# 6digit-ADC-display.net
KiCad netlist of a schematic drawn in EAGLE
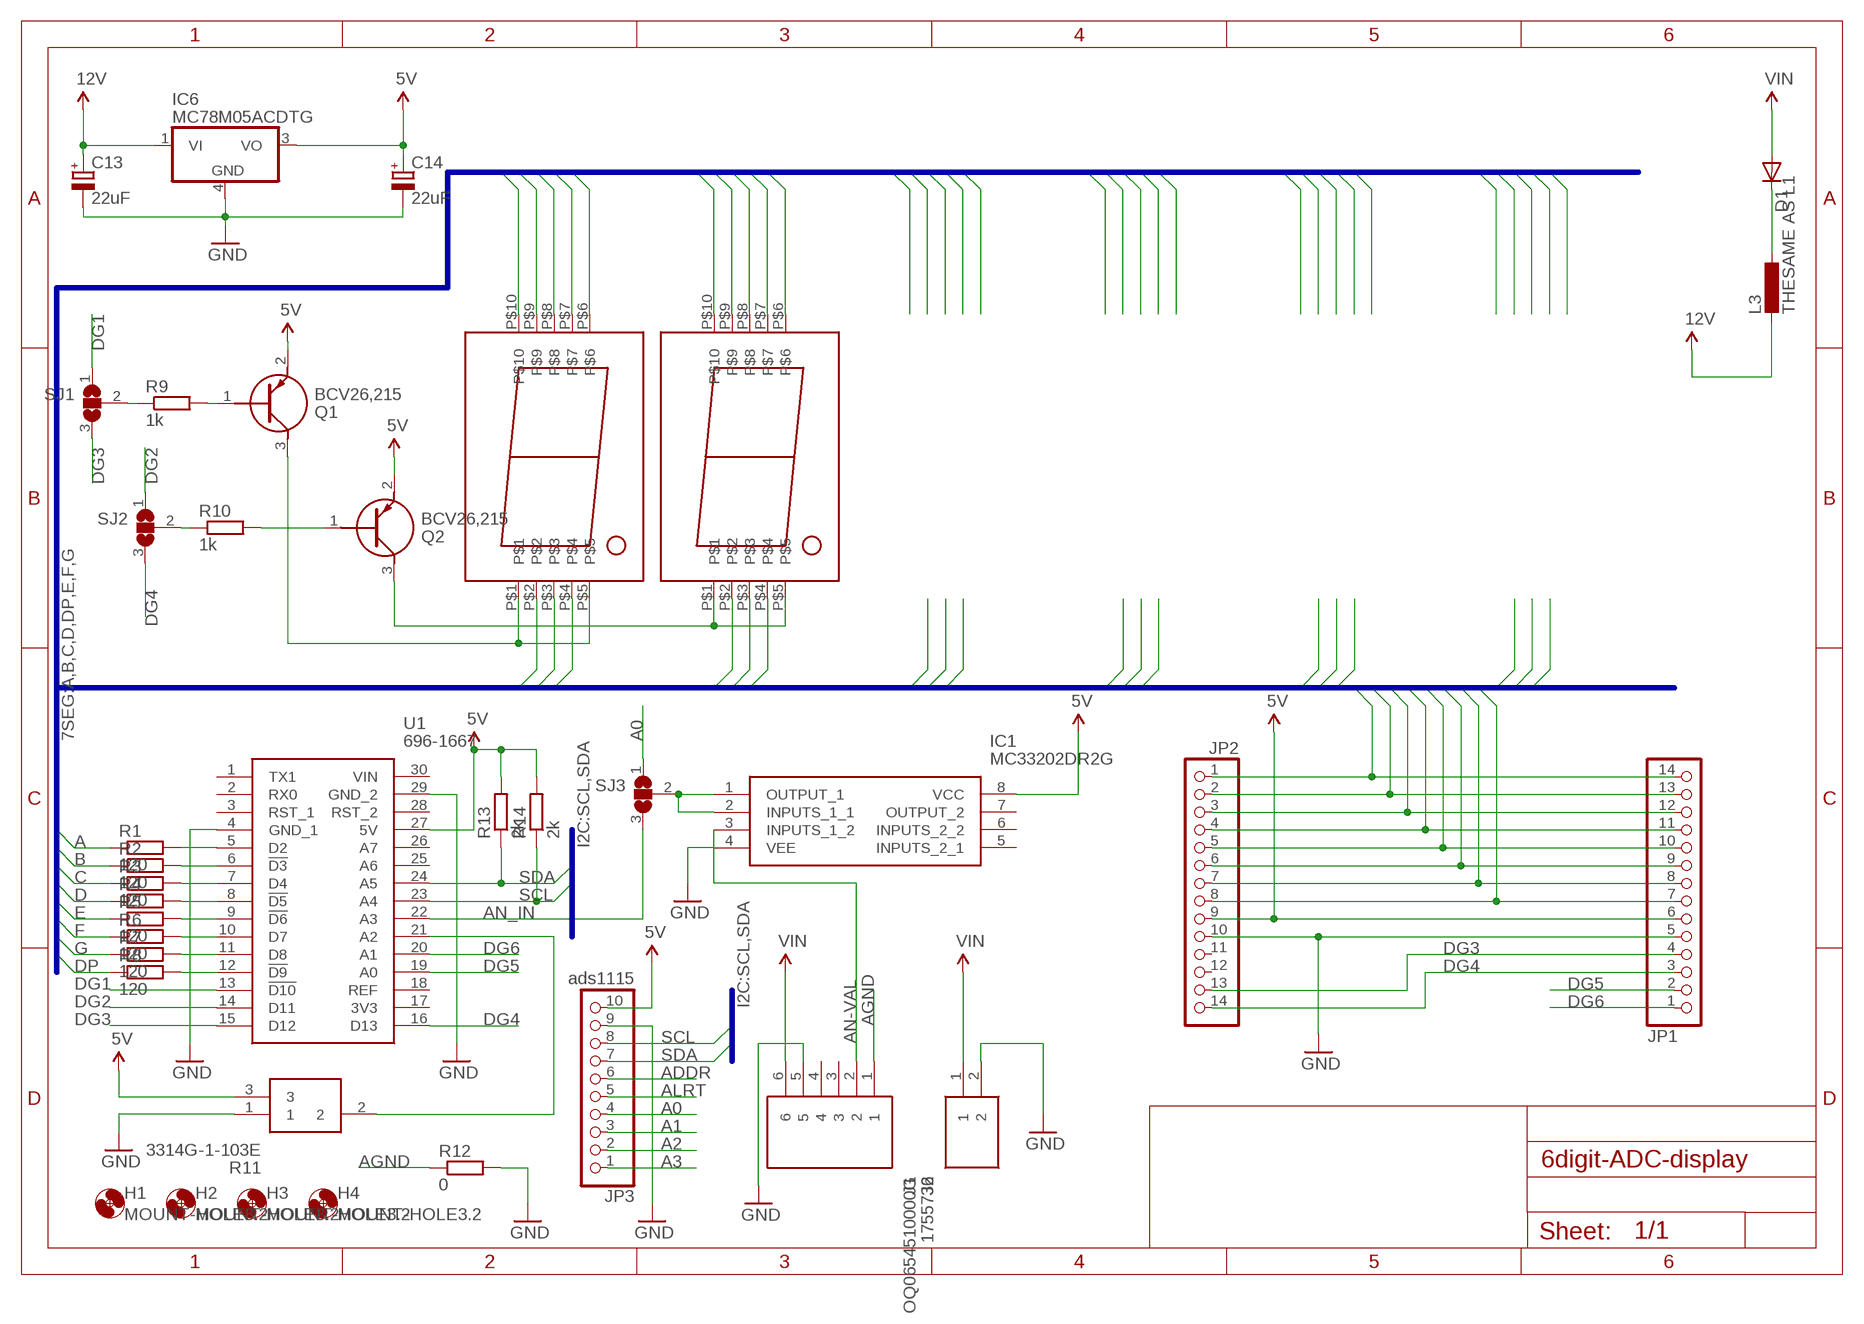
[diagram p0: schematic, sheet 1]

(export (version "E")
  (design (tool "Eeschema 10.0.6"))
  (components
    (comp (ref "C13")
      (value "22uF")
      (footprint "eagle-import:E2,5-7")
      (libsource (lib "eagle-import") (part "CPOL-EUE2.5-7"))
    )
    (comp (ref "C14")
      (value "22uF")
      (footprint "eagle-import:E2,5-7")
      (libsource (lib "eagle-import") (part "CPOL-EUE2.5-7"))
    )
    (comp (ref "D1")
      (value "DIODE-DO-214AC")
      (footprint "eagle-import:DO-214AC")
      (libsource (lib "eagle-import") (part "DIODE-DO-214AC"))
    )
    (comp (ref "H1")
      (value "MOUNT-HOLE3.2")
      (footprint "eagle-import:3,2")
      (libsource (lib "eagle-import") (part "MOUNT-HOLE3.2"))
    )
    (comp (ref "H2")
      (value "MOUNT-HOLE3.2")
      (footprint "eagle-import:3,2")
      (libsource (lib "eagle-import") (part "MOUNT-HOLE3.2"))
    )
    (comp (ref "H3")
      (value "MOUNT-HOLE3.2")
      (footprint "eagle-import:3,2")
      (libsource (lib "eagle-import") (part "MOUNT-HOLE3.2"))
    )
    (comp (ref "H4")
      (value "MOUNT-HOLE3.2")
      (footprint "eagle-import:3,2")
      (libsource (lib "eagle-import") (part "MOUNT-HOLE3.2"))
    )
    (comp (ref "IC1")
      (value "MC33202DR2G")
      (footprint "eagle-import:SOIC127P600X175-8N")
      (fields (field (name "MOUSER_PART_NUMBER") "863-MC33202DR2G"))
      (libsource (lib "eagle-import") (part "MC33202DR2G"))
    )
    (comp (ref "IC6")
      (value "MC78M05ACDTG")
      (footprint "eagle-import:DPACK_3")
      (libsource (lib "eagle-import") (part "MC78M05ACDTG"))
    )
    (comp (ref "J1")
      (value "1755736")
      (footprint "eagle-import:SHDR2W100P0X508_1X2_1216X860X1")
      (fields (field (name "MOUSER_PART_NUMBER") "651-1755736"))
      (libsource (lib "eagle-import") (part "1755736"))
    )
    (comp (ref "J2")
      (value "OQ0654510000G")
      (footprint "eagle-import:SHDRRA6W100P0X508_1X6_3248X120")
      (fields (field (name "MOUSER_PART_NUMBER") "649-OQ06545100J0G"))
      (libsource (lib "eagle-import") (part "OQ0654510000G"))
    )
    (comp (ref "JP1")
      (value "PINHD-1X14/90")
      (footprint "eagle-import:1X14_90")
      (libsource (lib "eagle-import") (part "PINHD-1X14/90"))
    )
    (comp (ref "JP2")
      (value "PINHD-1X14/90")
      (footprint "eagle-import:1X14_90")
      (libsource (lib "eagle-import") (part "PINHD-1X14/90"))
    )
    (comp (ref "JP3")
      (value "ads1115")
      (footprint "eagle-import:1X10")
      (libsource (lib "eagle-import") (part "PINHD-1X10"))
    )
    (comp (ref "L3")
      (value "THESAME AS L1")
      (footprint "eagle-import:L1812")
      (libsource (lib "eagle-import") (part "L-EUL1812"))
    )
    (comp (ref "Q1")
      (value "BCV26,215")
      (footprint "eagle-import:SOT95P230X110-3N")
      (fields (field (name "MOUSER_PART_NUMBER") "771-BCV26215"))
      (libsource (lib "eagle-import") (part "BCV26,215"))
    )
    (comp (ref "Q2")
      (value "BCV26,215")
      (footprint "eagle-import:SOT95P230X110-3N")
      (fields (field (name "MOUSER_PART_NUMBER") "771-BCV26215"))
      (libsource (lib "eagle-import") (part "BCV26,215"))
    )
    (comp (ref "R1")
      (value "120")
      (footprint "eagle-import:R0805")
      (libsource (lib "eagle-import") (part "R-EU_R0805"))
    )
    (comp (ref "R2")
      (value "120")
      (footprint "eagle-import:R0805")
      (libsource (lib "eagle-import") (part "R-EU_R0805"))
    )
    (comp (ref "R3")
      (value "120")
      (footprint "eagle-import:R0805")
      (libsource (lib "eagle-import") (part "R-EU_R0805"))
    )
    (comp (ref "R4")
      (value "R-EU_R0805")
      (footprint "eagle-import:R0805")
      (libsource (lib "eagle-import") (part "R-EU_R0805"))
    )
    (comp (ref "R5")
      (value "120")
      (footprint "eagle-import:R0805")
      (libsource (lib "eagle-import") (part "R-EU_R0805"))
    )
    (comp (ref "R6")
      (value "120")
      (footprint "eagle-import:R0805")
      (libsource (lib "eagle-import") (part "R-EU_R0805"))
    )
    (comp (ref "R7")
      (value "120")
      (footprint "eagle-import:R0805")
      (libsource (lib "eagle-import") (part "R-EU_R0805"))
    )
    (comp (ref "R8")
      (value "120")
      (footprint "eagle-import:R0805")
      (libsource (lib "eagle-import") (part "R-EU_R0805"))
    )
    (comp (ref "R9")
      (value "1k")
      (footprint "eagle-import:R0805")
      (libsource (lib "eagle-import") (part "R-EU_R0805"))
    )
    (comp (ref "R10")
      (value "1k")
      (footprint "eagle-import:R0805")
      (libsource (lib "eagle-import") (part "R-EU_R0805"))
    )
    (comp (ref "R11")
      (value "3314G-1-103E")
      (footprint "eagle-import:3314G-1-102E")
      (fields (field (name "MOUSER_PART_NUMBER") "652-3314G-1-103E"))
      (libsource (lib "eagle-import") (part "3314G-1-103E"))
    )
    (comp (ref "R12")
      (value "0")
      (footprint "eagle-import:R0805")
      (libsource (lib "eagle-import") (part "R-EU_R0805"))
    )
    (comp (ref "R13")
      (value "2k")
      (footprint "eagle-import:R0805")
      (libsource (lib "eagle-import") (part "R-EU_R0805"))
    )
    (comp (ref "R14")
      (value "2k")
      (footprint "eagle-import:R0805")
      (libsource (lib "eagle-import") (part "R-EU_R0805"))
    )
    (comp (ref "SJ1")
      (value "SJ2W")
      (footprint "eagle-import:SJ_2")
      (libsource (lib "eagle-import") (part "SJ2W"))
    )
    (comp (ref "SJ2")
      (value "SJ2W")
      (footprint "eagle-import:SJ_2")
      (libsource (lib "eagle-import") (part "SJ2W"))
    )
    (comp (ref "SJ3")
      (value "SJ2W")
      (footprint "eagle-import:SJ_2")
      (libsource (lib "eagle-import") (part "SJ2W"))
    )
    (comp (ref "U$1")
      (value "TOS-23101BMRL-B")
      (footprint "eagle-import:TOS-23101BMRL-B")
      (libsource (lib "eagle-import") (part "TOS-23101BMRL-B"))
    )
    (comp (ref "U$2")
      (value "TOS-23101BMRL-B")
      (footprint "eagle-import:TOS-23101BMRL-B")
      (libsource (lib "eagle-import") (part "TOS-23101BMRL-B"))
    )
    (comp (ref "U1")
      (value "696-1667")
      (footprint "eagle-import:6961667")
      (libsource (lib "eagle-import") (part "696-1667"))
    )
  )
  (nets
    (net (code "3") (name "/A") (class "Default")
      (node (ref "JP1") (pin "14") (pinfunction "14_14") (pintype "passive"))
      (node (ref "JP2") (pin "1") (pinfunction "1_1") (pintype "passive"))
      (node (ref "R1") (pin "1") (pinfunction "1_1") (pintype "passive"))
      (node (ref "U$1") (pin "P$7") (pinfunction "P$7_P$7") (pintype "bidirectional"))
      (node (ref "U$2") (pin "P$7") (pinfunction "P$7_P$7") (pintype "bidirectional"))
    )
    (net (code "4") (name "/A0") (class "Default")
      (node (ref "JP3") (pin "4") (pinfunction "4_4") (pintype "passive"))
      (node (ref "SJ3") (pin "1") (pinfunction "1_1") (pintype "passive"))
    )
    (net (code "5") (name "/A1") (class "Default")
      (node (ref "JP3") (pin "3") (pinfunction "3_3") (pintype "passive"))
    )
    (net (code "6") (name "/A2") (class "Default")
      (node (ref "JP3") (pin "2") (pinfunction "2_2") (pintype "passive"))
    )
    (net (code "7") (name "/A3") (class "Default")
      (node (ref "JP3") (pin "1") (pinfunction "1_1") (pintype "passive"))
    )
    (net (code "8") (name "/ADDR") (class "Default")
      (node (ref "JP3") (pin "6") (pinfunction "6_6") (pintype "passive"))
    )
    (net (code "9") (name "/AGND") (class "Default")
      (node (ref "J2") (pin "1") (pinfunction "1_1") (pintype "bidirectional"))
      (node (ref "R12") (pin "1") (pinfunction "1_1") (pintype "passive"))
    )
    (net (code "10") (name "/ALRT") (class "Default")
      (node (ref "JP3") (pin "5") (pinfunction "5_5") (pintype "passive"))
    )
    (net (code "11") (name "/AN-VAL") (class "Default")
      (node (ref "IC1") (pin "3") (pinfunction "INPUTS_1_2_3") (pintype "bidirectional"))
      (node (ref "J2") (pin "2") (pinfunction "2_2") (pintype "bidirectional"))
    )
    (net (code "12") (name "/AN_IN") (class "Default")
      (node (ref "SJ3") (pin "3") (pinfunction "3_3") (pintype "passive"))
      (node (ref "U1") (pin "22") (pinfunction "A3_22") (pintype "bidirectional"))
    )
    (net (code "13") (name "/B") (class "Default")
      (node (ref "JP1") (pin "13") (pinfunction "13_13") (pintype "passive"))
      (node (ref "JP2") (pin "2") (pinfunction "2_2") (pintype "passive"))
      (node (ref "R2") (pin "1") (pinfunction "1_1") (pintype "passive"))
      (node (ref "U$1") (pin "P$6") (pinfunction "P$6_P$6") (pintype "bidirectional"))
      (node (ref "U$2") (pin "P$6") (pinfunction "P$6_P$6") (pintype "bidirectional"))
    )
    (net (code "14") (name "/C") (class "Default")
      (node (ref "JP1") (pin "12") (pinfunction "12_12") (pintype "passive"))
      (node (ref "JP2") (pin "3") (pinfunction "3_3") (pintype "passive"))
      (node (ref "R3") (pin "1") (pinfunction "1_1") (pintype "passive"))
      (node (ref "U$1") (pin "P$4") (pinfunction "P$4_P$4") (pintype "bidirectional"))
      (node (ref "U$2") (pin "P$4") (pinfunction "P$4_P$4") (pintype "bidirectional"))
    )
    (net (code "15") (name "/D") (class "Default")
      (node (ref "JP1") (pin "11") (pinfunction "11_11") (pintype "passive"))
      (node (ref "JP2") (pin "4") (pinfunction "4_4") (pintype "passive"))
      (node (ref "R4") (pin "1") (pinfunction "1_1") (pintype "passive"))
      (node (ref "U$1") (pin "P$3") (pinfunction "P$3_P$3") (pintype "bidirectional"))
      (node (ref "U$2") (pin "P$3") (pinfunction "P$3_P$3") (pintype "bidirectional"))
    )
    (net (code "16") (name "/DG1") (class "Default")
      (node (ref "SJ1") (pin "1") (pinfunction "1_1") (pintype "passive"))
      (node (ref "U1") (pin "13") (pinfunction "~{D10}_13") (pintype "bidirectional"))
    )
    (net (code "17") (name "/DG2") (class "Default")
      (node (ref "SJ2") (pin "1") (pinfunction "1_1") (pintype "passive"))
      (node (ref "U1") (pin "14") (pinfunction "D11_14") (pintype "bidirectional"))
    )
    (net (code "18") (name "/DG3") (class "Default")
      (node (ref "JP1") (pin "4") (pinfunction "4_4") (pintype "passive"))
      (node (ref "JP2") (pin "13") (pinfunction "13_13") (pintype "passive"))
      (node (ref "SJ1") (pin "3") (pinfunction "3_3") (pintype "passive"))
      (node (ref "U1") (pin "15") (pinfunction "D12_15") (pintype "bidirectional"))
    )
    (net (code "19") (name "/DG4") (class "Default")
      (node (ref "JP1") (pin "3") (pinfunction "3_3") (pintype "passive"))
      (node (ref "JP2") (pin "14") (pinfunction "14_14") (pintype "passive"))
      (node (ref "SJ2") (pin "3") (pinfunction "3_3") (pintype "passive"))
      (node (ref "U1") (pin "16") (pinfunction "D13_16") (pintype "bidirectional"))
    )
    (net (code "20") (name "/DG5") (class "Default")
      (node (ref "JP1") (pin "2") (pinfunction "2_2") (pintype "passive"))
      (node (ref "U1") (pin "19") (pinfunction "A0_19") (pintype "bidirectional"))
    )
    (net (code "21") (name "/DG6") (class "Default")
      (node (ref "JP1") (pin "1") (pinfunction "1_1") (pintype "passive"))
      (node (ref "U1") (pin "20") (pinfunction "A1_20") (pintype "bidirectional"))
    )
    (net (code "22") (name "/DP") (class "Default")
      (node (ref "JP1") (pin "7") (pinfunction "7_7") (pintype "passive"))
      (node (ref "JP2") (pin "8") (pinfunction "8_8") (pintype "passive"))
      (node (ref "R8") (pin "1") (pinfunction "1_1") (pintype "passive"))
      (node (ref "U$1") (pin "P$8") (pinfunction "P$8_P$8") (pintype "bidirectional"))
      (node (ref "U$2") (pin "P$8") (pinfunction "P$8_P$8") (pintype "bidirectional"))
    )
    (net (code "23") (name "/E") (class "Default")
      (node (ref "JP1") (pin "10") (pinfunction "10_10") (pintype "passive"))
      (node (ref "JP2") (pin "5") (pinfunction "5_5") (pintype "passive"))
      (node (ref "R5") (pin "1") (pinfunction "1_1") (pintype "passive"))
      (node (ref "U$1") (pin "P$2") (pinfunction "P$2_P$2") (pintype "bidirectional"))
      (node (ref "U$2") (pin "P$2") (pinfunction "P$2_P$2") (pintype "bidirectional"))
    )
    (net (code "24") (name "/F") (class "Default")
      (node (ref "JP1") (pin "9") (pinfunction "9_9") (pintype "passive"))
      (node (ref "JP2") (pin "6") (pinfunction "6_6") (pintype "passive"))
      (node (ref "R6") (pin "1") (pinfunction "1_1") (pintype "passive"))
      (node (ref "U$1") (pin "P$9") (pinfunction "P$9_P$9") (pintype "bidirectional"))
      (node (ref "U$2") (pin "P$9") (pinfunction "P$9_P$9") (pintype "bidirectional"))
    )
    (net (code "25") (name "/G") (class "Default")
      (node (ref "JP1") (pin "8") (pinfunction "8_8") (pintype "passive"))
      (node (ref "JP2") (pin "7") (pinfunction "7_7") (pintype "passive"))
      (node (ref "R7") (pin "1") (pinfunction "1_1") (pintype "passive"))
      (node (ref "U$1") (pin "P$10") (pinfunction "P$10_P$10") (pintype "bidirectional"))
      (node (ref "U$2") (pin "P$10") (pinfunction "P$10_P$10") (pintype "bidirectional"))
    )
    (net (code "26") (name "/SCL") (class "Default")
      (node (ref "JP3") (pin "8") (pinfunction "8_8") (pintype "passive"))
      (node (ref "R14") (pin "1") (pinfunction "1_1") (pintype "passive"))
      (node (ref "U1") (pin "23") (pinfunction "A4_23") (pintype "bidirectional"))
    )
    (net (code "27") (name "/SDA") (class "Default")
      (node (ref "JP3") (pin "7") (pinfunction "7_7") (pintype "passive"))
      (node (ref "R13") (pin "1") (pinfunction "1_1") (pintype "passive"))
      (node (ref "U1") (pin "24") (pinfunction "A5_24") (pintype "bidirectional"))
    )
    (net (code "30") (name "5V") (class "Default")
      (node (ref "C14") (pin "+") (pinfunction "+_+") (pintype "passive"))
      (node (ref "IC1") (pin "8") (pinfunction "VCC_8") (pintype "bidirectional"))
      (node (ref "IC6") (pin "3") (pinfunction "VO_3") (pintype "passive"))
      (node (ref "JP1") (pin "6") (pinfunction "6_6") (pintype "passive"))
      (node (ref "JP2") (pin "9") (pinfunction "9_9") (pintype "passive"))
      (node (ref "JP3") (pin "10") (pinfunction "10_10") (pintype "passive"))
      (node (ref "Q1") (pin "2") (pinfunction "E_2") (pintype "bidirectional"))
      (node (ref "Q2") (pin "2") (pinfunction "E_2") (pintype "bidirectional"))
      (node (ref "R11") (pin "3") (pinfunction "3_3") (pintype "bidirectional"))
      (node (ref "R13") (pin "2") (pinfunction "2_2") (pintype "passive"))
      (node (ref "R14") (pin "2") (pinfunction "2_2") (pintype "passive"))
      (node (ref "U1") (pin "27") (pinfunction "5V_27") (pintype "bidirectional"))
    )
    (net (code "31") (name "12V") (class "Default")
      (node (ref "C13") (pin "+") (pinfunction "+_+") (pintype "passive"))
      (node (ref "IC6") (pin "1") (pinfunction "VI_1") (pintype "input"))
      (node (ref "L3") (pin "2") (pinfunction "2_2") (pintype "passive"))
    )
    (net (code "32") (name "GND") (class "Default")
      (node (ref "C13") (pin "-") (pinfunction "-_-") (pintype "passive"))
      (node (ref "C14") (pin "-") (pinfunction "-_-") (pintype "passive"))
      (node (ref "IC1") (pin "4") (pinfunction "VEE_4") (pintype "bidirectional"))
      (node (ref "IC6") (pin "4") (pinfunction "GND_4") (pintype "passive"))
      (node (ref "J1") (pin "2") (pinfunction "2_2") (pintype "bidirectional"))
      (node (ref "J2") (pin "5") (pinfunction "5_5") (pintype "bidirectional"))
      (node (ref "JP1") (pin "5") (pinfunction "5_5") (pintype "passive"))
      (node (ref "JP2") (pin "10") (pinfunction "10_10") (pintype "passive"))
      (node (ref "JP3") (pin "9") (pinfunction "9_9") (pintype "passive"))
      (node (ref "R11") (pin "1") (pinfunction "1_1") (pintype "bidirectional"))
      (node (ref "R12") (pin "2") (pinfunction "2_2") (pintype "passive"))
      (node (ref "U1") (pin "29") (pinfunction "GND_2_29") (pintype "bidirectional"))
      (node (ref "U1") (pin "4") (pinfunction "GND_1_4") (pintype "bidirectional"))
    )
    (net (code "33") (name "Net-(D1-C)") (class "Default")
      (node (ref "D1") (pin "1") (pinfunction "C_1") (pintype "passive"))
      (node (ref "L3") (pin "1") (pinfunction "1_1") (pintype "passive"))
    )
    (net (code "34") (name "Net-(IC1-INPUTS_1_1)") (class "Default")
      (node (ref "IC1") (pin "1") (pinfunction "OUTPUT_1_1") (pintype "bidirectional"))
      (node (ref "IC1") (pin "2") (pinfunction "INPUTS_1_1_2") (pintype "bidirectional"))
      (node (ref "SJ3") (pin "2") (pinfunction "2_2") (pintype "passive"))
    )
    (net (code "35") (name "Net-(Q1-B)") (class "Default")
      (node (ref "Q1") (pin "1") (pinfunction "B_1") (pintype "bidirectional"))
      (node (ref "R9") (pin "2") (pinfunction "2_2") (pintype "passive"))
    )
    (net (code "36") (name "Net-(Q1-C)") (class "Default")
      (node (ref "Q1") (pin "3") (pinfunction "C_3") (pintype "bidirectional"))
      (node (ref "U$1") (pin "P$1") (pinfunction "P$1_P$1") (pintype "bidirectional"))
      (node (ref "U$1") (pin "P$5") (pinfunction "P$5_P$5") (pintype "bidirectional"))
    )
    (net (code "37") (name "Net-(Q2-B)") (class "Default")
      (node (ref "Q2") (pin "1") (pinfunction "B_1") (pintype "bidirectional"))
      (node (ref "R10") (pin "2") (pinfunction "2_2") (pintype "passive"))
    )
    (net (code "38") (name "Net-(Q2-C)") (class "Default")
      (node (ref "Q2") (pin "3") (pinfunction "C_3") (pintype "bidirectional"))
      (node (ref "U$2") (pin "P$1") (pinfunction "P$1_P$1") (pintype "bidirectional"))
      (node (ref "U$2") (pin "P$5") (pinfunction "P$5_P$5") (pintype "bidirectional"))
    )
    (net (code "39") (name "Net-(R9-Pad1)") (class "Default")
      (node (ref "R9") (pin "1") (pinfunction "1_1") (pintype "passive"))
      (node (ref "SJ1") (pin "2") (pinfunction "2_2") (pintype "passive"))
    )
    (net (code "40") (name "Net-(R10-Pad1)") (class "Default")
      (node (ref "R10") (pin "1") (pinfunction "1_1") (pintype "passive"))
      (node (ref "SJ2") (pin "2") (pinfunction "2_2") (pintype "passive"))
    )
    (net (code "41") (name "Net-(U1-A2)") (class "Default")
      (node (ref "R11") (pin "2") (pinfunction "2_2") (pintype "bidirectional"))
      (node (ref "U1") (pin "21") (pinfunction "A2_21") (pintype "bidirectional"))
    )
    (net (code "42") (name "Net-(U1-D2)") (class "Default")
      (node (ref "R1") (pin "2") (pinfunction "2_2") (pintype "passive"))
      (node (ref "U1") (pin "5") (pinfunction "D2_5") (pintype "bidirectional"))
    )
    (net (code "43") (name "Net-(U1-D4)") (class "Default")
      (node (ref "R3") (pin "2") (pinfunction "2_2") (pintype "passive"))
      (node (ref "U1") (pin "7") (pinfunction "D4_7") (pintype "bidirectional"))
    )
    (net (code "44") (name "Net-(U1-D7)") (class "Default")
      (node (ref "R6") (pin "2") (pinfunction "2_2") (pintype "passive"))
      (node (ref "U1") (pin "10") (pinfunction "D7_10") (pintype "bidirectional"))
    )
    (net (code "45") (name "Net-(U1-D8)") (class "Default")
      (node (ref "R7") (pin "2") (pinfunction "2_2") (pintype "passive"))
      (node (ref "U1") (pin "11") (pinfunction "D8_11") (pintype "bidirectional"))
    )
    (net (code "46") (name "Net-(U1-~{D3})") (class "Default")
      (node (ref "R2") (pin "2") (pinfunction "2_2") (pintype "passive"))
      (node (ref "U1") (pin "6") (pinfunction "~{D3}_6") (pintype "bidirectional"))
    )
    (net (code "47") (name "Net-(U1-~{D5})") (class "Default")
      (node (ref "R4") (pin "2") (pinfunction "2_2") (pintype "passive"))
      (node (ref "U1") (pin "8") (pinfunction "~{D5}_8") (pintype "bidirectional"))
    )
    (net (code "48") (name "Net-(U1-~{D6})") (class "Default")
      (node (ref "R5") (pin "2") (pinfunction "2_2") (pintype "passive"))
      (node (ref "U1") (pin "9") (pinfunction "~{D6}_9") (pintype "bidirectional"))
    )
    (net (code "49") (name "Net-(U1-~{D9})") (class "Default")
      (node (ref "R8") (pin "2") (pinfunction "2_2") (pintype "passive"))
      (node (ref "U1") (pin "12") (pinfunction "~{D9}_12") (pintype "bidirectional"))
    )
    (net (code "50") (name "VIN") (class "Default")
      (node (ref "D1") (pin "2") (pinfunction "A_2") (pintype "passive"))
      (node (ref "J1") (pin "1") (pinfunction "1_1") (pintype "bidirectional"))
      (node (ref "J2") (pin "6") (pinfunction "6_6") (pintype "bidirectional"))
    )
    (net (code "51") (name "unconnected-(IC1-INPUTS_2_1-Pad5)") (class "Default")
      (node (ref "IC1") (pin "5") (pinfunction "INPUTS_2_1_5") (pintype "bidirectional"))
    )
    (net (code "52") (name "unconnected-(IC1-INPUTS_2_2-Pad6)") (class "Default")
      (node (ref "IC1") (pin "6") (pinfunction "INPUTS_2_2_6") (pintype "bidirectional"))
    )
    (net (code "53") (name "unconnected-(IC1-OUTPUT_2-Pad7)") (class "Default")
      (node (ref "IC1") (pin "7") (pinfunction "OUTPUT_2_7") (pintype "bidirectional"))
    )
    (net (code "54") (name "unconnected-(J2-Pad3)") (class "Default")
      (node (ref "J2") (pin "3") (pinfunction "3_3") (pintype "bidirectional"))
    )
    (net (code "55") (name "unconnected-(J2-Pad4)") (class "Default")
      (node (ref "J2") (pin "4") (pinfunction "4_4") (pintype "bidirectional"))
    )
    (net (code "56") (name "unconnected-(JP2-Pad11)") (class "Default")
      (node (ref "JP2") (pin "11") (pinfunction "11_11") (pintype "passive"))
    )
    (net (code "57") (name "unconnected-(JP2-Pad12)") (class "Default")
      (node (ref "JP2") (pin "12") (pinfunction "12_12") (pintype "passive"))
    )
    (net (code "58") (name "unconnected-(U1-3V3-Pad17)") (class "Default")
      (node (ref "U1") (pin "17") (pinfunction "3V3_17") (pintype "bidirectional"))
    )
    (net (code "59") (name "unconnected-(U1-A6-Pad25)") (class "Default")
      (node (ref "U1") (pin "25") (pinfunction "A6_25") (pintype "bidirectional"))
    )
    (net (code "60") (name "unconnected-(U1-A7-Pad26)") (class "Default")
      (node (ref "U1") (pin "26") (pinfunction "A7_26") (pintype "bidirectional"))
    )
    (net (code "61") (name "unconnected-(U1-REF-Pad18)") (class "Default")
      (node (ref "U1") (pin "18") (pinfunction "REF_18") (pintype "bidirectional"))
    )
    (net (code "62") (name "unconnected-(U1-RST_1-Pad3)") (class "Default")
      (node (ref "U1") (pin "3") (pinfunction "RST_1_3") (pintype "bidirectional"))
    )
    (net (code "63") (name "unconnected-(U1-RST_2-Pad28)") (class "Default")
      (node (ref "U1") (pin "28") (pinfunction "RST_2_28") (pintype "bidirectional"))
    )
    (net (code "64") (name "unconnected-(U1-RX0-Pad2)") (class "Default")
      (node (ref "U1") (pin "2") (pinfunction "RX0_2") (pintype "bidirectional"))
    )
    (net (code "65") (name "unconnected-(U1-TX1-Pad1)") (class "Default")
      (node (ref "U1") (pin "1") (pinfunction "TX1_1") (pintype "bidirectional"))
    )
    (net (code "66") (name "unconnected-(U1-VIN-Pad30)") (class "Default")
      (node (ref "U1") (pin "30") (pinfunction "VIN_30") (pintype "bidirectional"))
    )
  )
)
